# 3comando.net
KiCad netlist of a schematic drawn in EAGLE
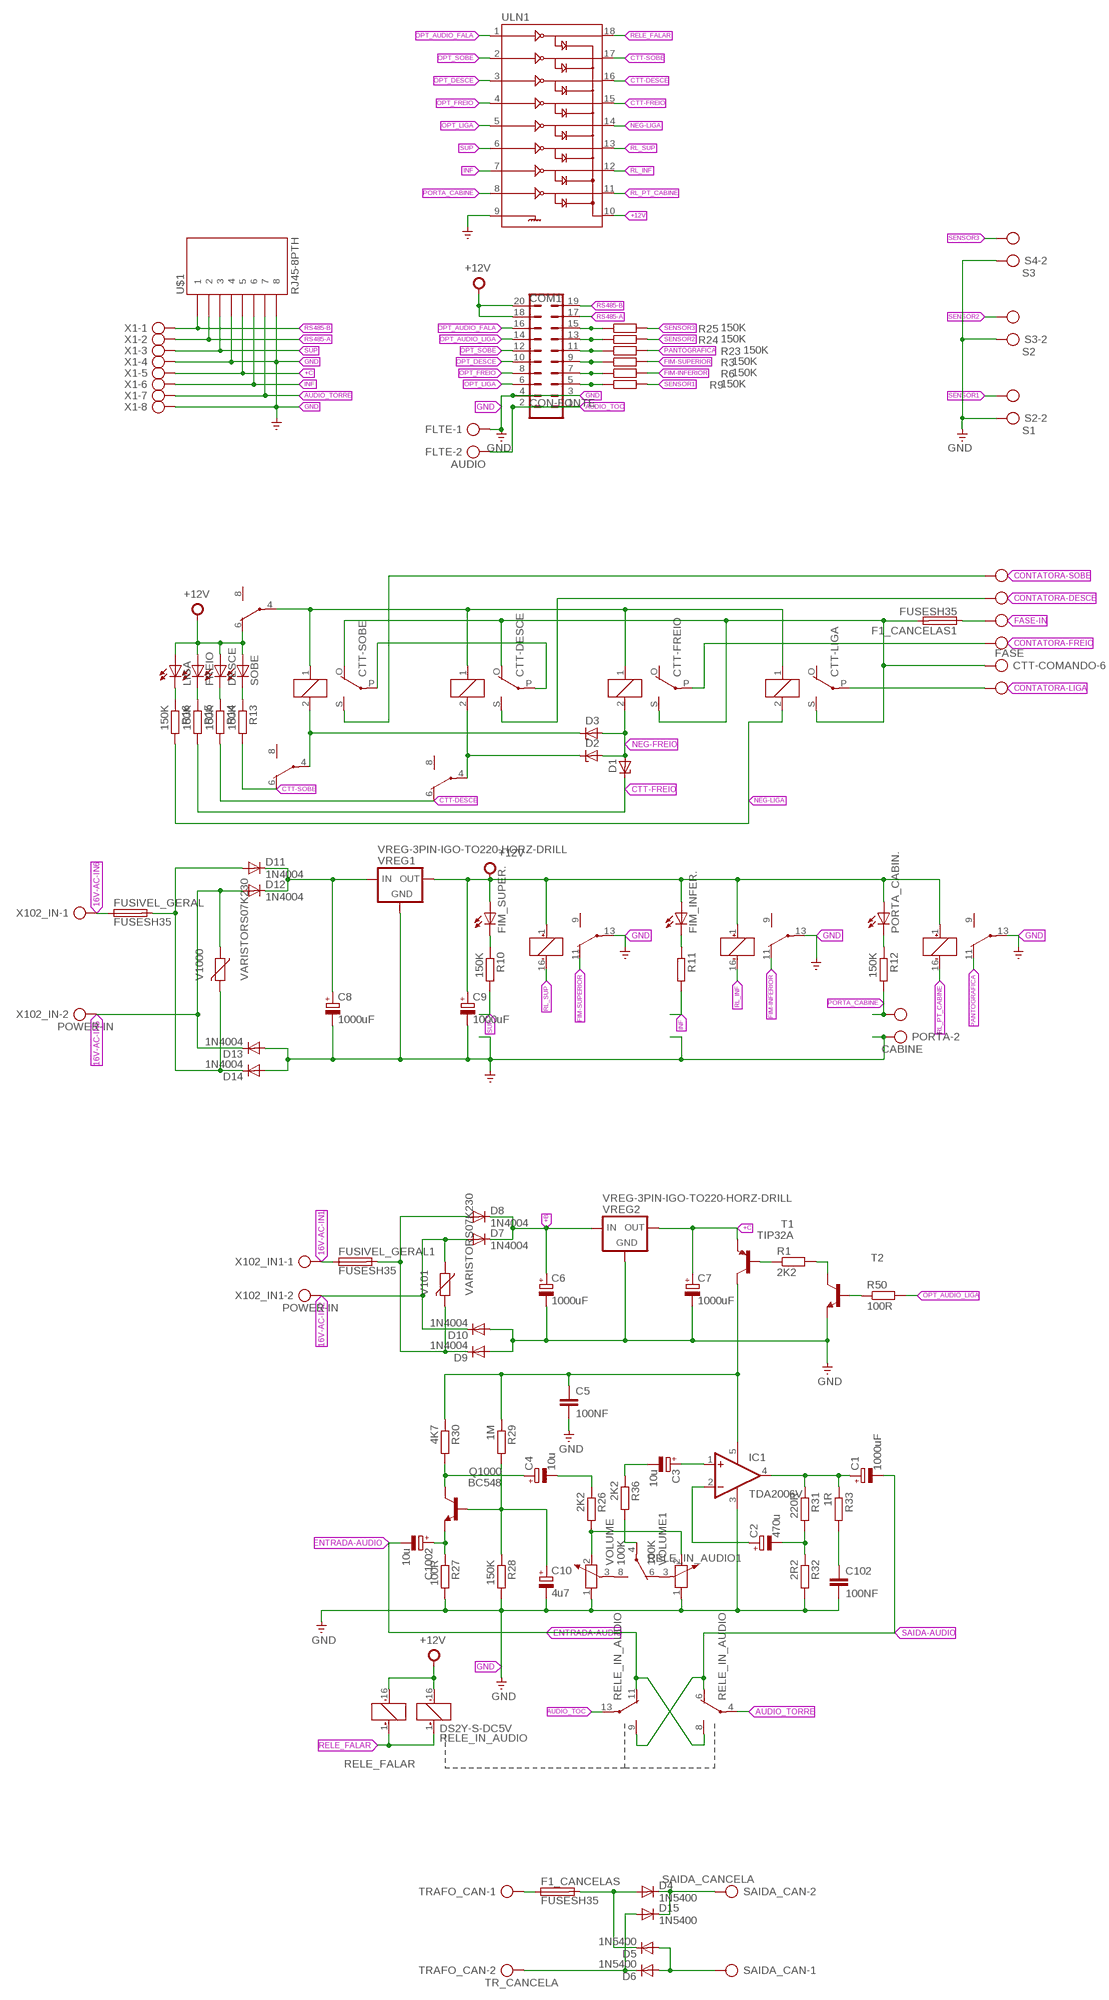
[diagram p0: schematic, sheet 1]

(export (version "E")
  (design (tool "Eeschema 10.0.6"))
  (components
    (comp (ref "C1")
      (value "1000uF")
      (footprint "eagle-import:TAP5-80")
      (libsource (lib "eagle-import") (part "CPOL-EUTAP5-80"))
    )
    (comp (ref "C2")
      (value "470u")
      (footprint "eagle-import:TAP5-80")
      (libsource (lib "eagle-import") (part "CPOL-EUTAP5-80"))
    )
    (comp (ref "C3")
      (value "10u")
      (footprint "eagle-import:TAP5-45")
      (libsource (lib "eagle-import") (part "CPOL-EUTAP5-45"))
    )
    (comp (ref "C4")
      (value "10u")
      (footprint "eagle-import:TAP5-45")
      (libsource (lib "eagle-import") (part "CPOL-EUTAP5-45"))
    )
    (comp (ref "C5")
      (value "100NF")
      (footprint "eagle-import:C050-030X075")
      (libsource (lib "eagle-import") (part "C-EU050-030X075"))
    )
    (comp (ref "C6")
      (value "1000uF")
      (footprint "eagle-import:TAP5-80")
      (libsource (lib "eagle-import") (part "CPOL-EUTAP5-80"))
    )
    (comp (ref "C7")
      (value "1000uF")
      (footprint "eagle-import:TAP5-80")
      (libsource (lib "eagle-import") (part "CPOL-EUTAP5-80"))
    )
    (comp (ref "C8")
      (value "1000uF")
      (footprint "eagle-import:TAP5-80")
      (libsource (lib "eagle-import") (part "CPOL-EUTAP5-80"))
    )
    (comp (ref "C9")
      (value "1000uF")
      (footprint "eagle-import:TAP5-80")
      (libsource (lib "eagle-import") (part "CPOL-EUTAP5-80"))
    )
    (comp (ref "C10")
      (value "4u7")
      (footprint "eagle-import:TAP5-45")
      (libsource (lib "eagle-import") (part "CPOL-EUTAP5-45"))
    )
    (comp (ref "C102")
      (value "100NF")
      (footprint "eagle-import:C050-030X075")
      (libsource (lib "eagle-import") (part "C-EU050-030X075"))
    )
    (comp (ref "C1002")
      (value "10u")
      (footprint "eagle-import:TAP5-45")
      (libsource (lib "eagle-import") (part "CPOL-EUTAP5-45"))
    )
    (comp (ref "COM1")
      (value "CON-FONTE")
      (footprint "eagle-import:ML20")
      (libsource (lib "eagle-import") (part "ML20"))
    )
    (comp (ref "CTT-COMANDO")
      (value "FASE")
      (footprint "eagle-import:AK500_6")
      (libsource (lib "eagle-import") (part "AK500/6"))
    )
    (comp (ref "CTT-DESCE")
      (value "G5L")
      (footprint "eagle-import:G5LE")
      (libsource (lib "eagle-import") (part "G5L"))
    )
    (comp (ref "CTT-FREIO")
      (value "G5L")
      (footprint "eagle-import:G5LE")
      (libsource (lib "eagle-import") (part "G5L"))
    )
    (comp (ref "CTT-LIGA")
      (value "G5L")
      (footprint "eagle-import:G5LE")
      (libsource (lib "eagle-import") (part "G5L"))
    )
    (comp (ref "CTT-SOBE")
      (value "G5L")
      (footprint "eagle-import:G5LE")
      (libsource (lib "eagle-import") (part "G5L"))
    )
    (comp (ref "D1")
      (value "ZENER-DIODEZD-7.5")
      (footprint "eagle-import:ZDIO-7.5")
      (libsource (lib "eagle-import") (part "ZENER-DIODEZD-7.5"))
    )
    (comp (ref "D2")
      (value "ZENER-DIODEZD-7.5")
      (footprint "eagle-import:ZDIO-7.5")
      (libsource (lib "eagle-import") (part "ZENER-DIODEZD-7.5"))
    )
    (comp (ref "D3")
      (value "ZENER-DIODEZD-7.5")
      (footprint "eagle-import:ZDIO-7.5")
      (libsource (lib "eagle-import") (part "ZENER-DIODEZD-7.5"))
    )
    (comp (ref "D4")
      (value "1N5400")
      (footprint "eagle-import:DO201-15")
      (libsource (lib "eagle-import") (part "1N5400"))
    )
    (comp (ref "D5")
      (value "1N5400")
      (footprint "eagle-import:DO201-15")
      (libsource (lib "eagle-import") (part "1N5400"))
    )
    (comp (ref "D6")
      (value "1N5400")
      (footprint "eagle-import:DO201-15")
      (libsource (lib "eagle-import") (part "1N5400"))
    )
    (comp (ref "D7")
      (value "1N4004")
      (footprint "eagle-import:DO41-10")
      (libsource (lib "eagle-import") (part "1N4004"))
    )
    (comp (ref "D8")
      (value "1N4004")
      (footprint "eagle-import:DO41-10")
      (libsource (lib "eagle-import") (part "1N4004"))
    )
    (comp (ref "D9")
      (value "1N4004")
      (footprint "eagle-import:DO41-10")
      (libsource (lib "eagle-import") (part "1N4004"))
    )
    (comp (ref "D10")
      (value "1N4004")
      (footprint "eagle-import:DO41-10")
      (libsource (lib "eagle-import") (part "1N4004"))
    )
    (comp (ref "D11")
      (value "1N4004")
      (footprint "eagle-import:DO41-10")
      (libsource (lib "eagle-import") (part "1N4004"))
    )
    (comp (ref "D12")
      (value "1N4004")
      (footprint "eagle-import:DO41-10")
      (libsource (lib "eagle-import") (part "1N4004"))
    )
    (comp (ref "D13")
      (value "1N4004")
      (footprint "eagle-import:DO41-10")
      (libsource (lib "eagle-import") (part "1N4004"))
    )
    (comp (ref "D14")
      (value "1N4004")
      (footprint "eagle-import:DO41-10")
      (libsource (lib "eagle-import") (part "1N4004"))
    )
    (comp (ref "D15")
      (value "1N5400")
      (footprint "eagle-import:DO201-15")
      (libsource (lib "eagle-import") (part "1N5400"))
    )
    (comp (ref "DESCE")
      (value "LED5MM")
      (footprint "eagle-import:LED5MM")
      (libsource (lib "eagle-import") (part "LED5MM"))
    )
    (comp (ref "F1_CANCELAS")
      (value "FUSESH35")
      (footprint "eagle-import:SH25")
      (libsource (lib "eagle-import") (part "FUSESH35"))
    )
    (comp (ref "F1_CANCELAS1")
      (value "FUSESH35")
      (footprint "eagle-import:SH25")
      (libsource (lib "eagle-import") (part "FUSESH35"))
    )
    (comp (ref "FIM_INFER.")
      (value "LED5MM")
      (footprint "eagle-import:LED5MM")
      (libsource (lib "eagle-import") (part "LED5MM"))
    )
    (comp (ref "FIM_SUPER.")
      (value "LED5MM")
      (footprint "eagle-import:LED5MM")
      (libsource (lib "eagle-import") (part "LED5MM"))
    )
    (comp (ref "FLTE")
      (value "AUDIO")
      (footprint "eagle-import:AK500_2")
      (libsource (lib "eagle-import") (part "AK500/2"))
    )
    (comp (ref "FREIO")
      (value "LED5MM")
      (footprint "eagle-import:LED5MM")
      (libsource (lib "eagle-import") (part "LED5MM"))
    )
    (comp (ref "FUSIVEL_GERAL")
      (value "FUSESH35")
      (footprint "eagle-import:SH25")
      (libsource (lib "eagle-import") (part "FUSESH35"))
    )
    (comp (ref "FUSIVEL_GERAL1")
      (value "FUSESH35")
      (footprint "eagle-import:SH25")
      (libsource (lib "eagle-import") (part "FUSESH35"))
    )
    (comp (ref "IC1")
      (value "TDA2006V")
      (footprint "eagle-import:CB360")
      (libsource (lib "eagle-import") (part "TDA2006V"))
    )
    (comp (ref "LIGA")
      (value "LED5MM")
      (footprint "eagle-import:LED5MM")
      (libsource (lib "eagle-import") (part "LED5MM"))
    )
    (comp (ref "PORTA")
      (value "CABINE")
      (footprint "eagle-import:AK500_2")
      (libsource (lib "eagle-import") (part "AK500/2"))
    )
    (comp (ref "PORTA_CABIN.")
      (value "LED5MM")
      (footprint "eagle-import:LED5MM")
      (libsource (lib "eagle-import") (part "LED5MM"))
    )
    (comp (ref "PORTA_CABINE")
      (value "DS2Y-S-DC5V")
      (footprint "eagle-import:DS2Y")
      (libsource (lib "eagle-import") (part "DS2Y-S-DC5V"))
    )
    (comp (ref "Q1000")
      (value "BC548")
      (footprint "eagle-import:TO92-EBC")
      (libsource (lib "eagle-import") (part "BC548"))
    )
    (comp (ref "R1")
      (value "2K2")
      (footprint "eagle-import:0207_10")
      (libsource (lib "eagle-import") (part "R-EU_0207/10"))
    )
    (comp (ref "R3")
      (value "150K")
      (footprint "eagle-import:0207_10")
      (libsource (lib "eagle-import") (part "R-EU_0207/10"))
    )
    (comp (ref "R6")
      (value "150K")
      (footprint "eagle-import:0207_10")
      (libsource (lib "eagle-import") (part "R-EU_0207/10"))
    )
    (comp (ref "R9")
      (value "150K")
      (footprint "eagle-import:0207_10")
      (libsource (lib "eagle-import") (part "R-EU_0207/10"))
    )
    (comp (ref "R10")
      (value "150K")
      (footprint "eagle-import:0207_10")
      (libsource (lib "eagle-import") (part "R-EU_0207/10"))
    )
    (comp (ref "R11")
      (value "150K")
      (footprint "eagle-import:0207_10")
      (libsource (lib "eagle-import") (part "R-EU_0207/10"))
    )
    (comp (ref "R12")
      (value "150K")
      (footprint "eagle-import:0207_10")
      (libsource (lib "eagle-import") (part "R-EU_0207/10"))
    )
    (comp (ref "R13")
      (value "150K")
      (footprint "eagle-import:0207_10")
      (libsource (lib "eagle-import") (part "R-EU_0207/10"))
    )
    (comp (ref "R14")
      (value "150K")
      (footprint "eagle-import:0207_10")
      (libsource (lib "eagle-import") (part "R-EU_0207/10"))
    )
    (comp (ref "R15")
      (value "150K")
      (footprint "eagle-import:0207_10")
      (libsource (lib "eagle-import") (part "R-EU_0207/10"))
    )
    (comp (ref "R16")
      (value "150K")
      (footprint "eagle-import:0207_10")
      (libsource (lib "eagle-import") (part "R-EU_0207/10"))
    )
    (comp (ref "R23")
      (value "150K")
      (footprint "eagle-import:0207_10")
      (libsource (lib "eagle-import") (part "R-EU_0207/10"))
    )
    (comp (ref "R24")
      (value "150K")
      (footprint "eagle-import:0207_10")
      (libsource (lib "eagle-import") (part "R-EU_0207/10"))
    )
    (comp (ref "R25")
      (value "150K")
      (footprint "eagle-import:0207_10")
      (libsource (lib "eagle-import") (part "R-EU_0207/10"))
    )
    (comp (ref "R26")
      (value "2K2")
      (footprint "eagle-import:0207_10")
      (libsource (lib "eagle-import") (part "R-EU_0207/10"))
    )
    (comp (ref "R27")
      (value "100R")
      (footprint "eagle-import:0207_10")
      (libsource (lib "eagle-import") (part "R-EU_0207/10"))
    )
    (comp (ref "R28")
      (value "150K")
      (footprint "eagle-import:0207_10")
      (libsource (lib "eagle-import") (part "R-EU_0207/10"))
    )
    (comp (ref "R29")
      (value "1M")
      (footprint "eagle-import:0207_10")
      (libsource (lib "eagle-import") (part "R-EU_0207/10"))
    )
    (comp (ref "R30")
      (value "4K7")
      (footprint "eagle-import:0207_10")
      (libsource (lib "eagle-import") (part "R-EU_0207/10"))
    )
    (comp (ref "R31")
      (value "220R")
      (footprint "eagle-import:0207_10")
      (libsource (lib "eagle-import") (part "R-EU_0207/10"))
    )
    (comp (ref "R32")
      (value "2R2")
      (footprint "eagle-import:0207_10")
      (libsource (lib "eagle-import") (part "R-EU_0207/10"))
    )
    (comp (ref "R33")
      (value "1R")
      (footprint "eagle-import:0207_10")
      (libsource (lib "eagle-import") (part "R-EU_0207/10"))
    )
    (comp (ref "R36")
      (value "2K2")
      (footprint "eagle-import:0207_10")
      (libsource (lib "eagle-import") (part "R-EU_0207/10"))
    )
    (comp (ref "R50")
      (value "100R")
      (footprint "eagle-import:0207_10")
      (libsource (lib "eagle-import") (part "R-EU_0207/10"))
    )
    (comp (ref "RELE_IN_AUDIO")
      (value "DS2Y-S-DC5V")
      (footprint "eagle-import:DS2Y")
      (libsource (lib "eagle-import") (part "DS2Y-S-DC5V"))
    )
    (comp (ref "RELE_IN_AUDIO1")
      (value "DS2Y-S-DC5V")
      (footprint "eagle-import:DS2Y")
      (libsource (lib "eagle-import") (part "DS2Y-S-DC5V"))
    )
    (comp (ref "RL_FIM_INFERIOR")
      (value "DS2Y-S-DC5V")
      (footprint "eagle-import:DS2Y")
      (libsource (lib "eagle-import") (part "DS2Y-S-DC5V"))
    )
    (comp (ref "RL_FIM_SUPERIOR")
      (value "DS2Y-S-DC5V")
      (footprint "eagle-import:DS2Y")
      (libsource (lib "eagle-import") (part "DS2Y-S-DC5V"))
    )
    (comp (ref "S2")
      (value "S1")
      (footprint "eagle-import:AK500_2")
      (libsource (lib "eagle-import") (part "AK500/2"))
    )
    (comp (ref "S3")
      (value "S2")
      (footprint "eagle-import:AK500_2")
      (libsource (lib "eagle-import") (part "AK500/2"))
    )
    (comp (ref "S4")
      (value "S3")
      (footprint "eagle-import:AK500_2")
      (libsource (lib "eagle-import") (part "AK500/2"))
    )
    (comp (ref "SAIDA_CAN")
      (value "SAIDA_CANCELA")
      (footprint "eagle-import:AK500_2")
      (libsource (lib "eagle-import") (part "AK500/2"))
    )
    (comp (ref "SOBE")
      (value "LED5MM")
      (footprint "eagle-import:LED5MM")
      (libsource (lib "eagle-import") (part "LED5MM"))
    )
    (comp (ref "T1")
      (value "TIP32A")
      (footprint "eagle-import:TO220")
      (libsource (lib "eagle-import") (part "TIP32A"))
    )
    (comp (ref "T2")
      (value "BC548-NPN-TO92-CBE")
      (footprint "eagle-import:TO92-CBE")
      (libsource (lib "eagle-import") (part "-NPN-TO92-CBEBC548"))
    )
    (comp (ref "TRAFO_CAN")
      (value "TR_CANCELA")
      (footprint "eagle-import:AK500_2")
      (libsource (lib "eagle-import") (part "AK500/2"))
    )
    (comp (ref "U$1")
      (value "RJ45-8PTH")
      (footprint "eagle-import:RJ45-8")
      (libsource (lib "eagle-import") (part "RJ45-8PTH"))
    )
    (comp (ref "ULN1")
      (value "ULN2803DIP")
      (footprint "eagle-import:DIL18")
      (libsource (lib "eagle-import") (part "ULN2803DIP"))
    )
    (comp (ref "V101")
      (value "VARISTORS07K230")
      (footprint "eagle-import:S07K230")
      (libsource (lib "eagle-import") (part "VARISTORS07K230"))
    )
    (comp (ref "V1000")
      (value "VARISTORS07K230")
      (footprint "eagle-import:S07K230")
      (libsource (lib "eagle-import") (part "VARISTORS07K230"))
    )
    (comp (ref "VOLUME")
      (value "100K")
      (footprint "eagle-import:PT-10")
      (libsource (lib "eagle-import") (part "POTENTIOMETER_PT-10"))
    )
    (comp (ref "VOLUME1")
      (value "100K")
      (footprint "eagle-import:PT-10")
      (libsource (lib "eagle-import") (part "POTENTIOMETER_PT-10"))
    )
    (comp (ref "VREG1")
      (value "VREG-3PIN-IGO-TO220-HORZ-DRILL")
      (footprint "eagle-import:TO220-HORZ-DRILL")
      (libsource (lib "eagle-import") (part "VREG-3PIN-IGO-TO220-HORZ-DRILL"))
    )
    (comp (ref "VREG2")
      (value "VREG-3PIN-IGO-TO220-HORZ-DRILL")
      (footprint "eagle-import:TO220-HORZ-DRILL")
      (libsource (lib "eagle-import") (part "VREG-3PIN-IGO-TO220-HORZ-DRILL"))
    )
    (comp (ref "X1")
      (value "RS485_CNT")
      (footprint "eagle-import:AK500_8")
      (libsource (lib "eagle-import") (part "AK500/8"))
    )
    (comp (ref "X102_IN")
      (value "POWER-IN")
      (footprint "eagle-import:AK500_2")
      (libsource (lib "eagle-import") (part "AK500/2"))
    )
    (comp (ref "X102_IN1")
      (value "POWER-IN")
      (footprint "eagle-import:AK500_2")
      (libsource (lib "eagle-import") (part "AK500/2"))
    )
  )
  (nets
    (net (code "1") (name "+12V") (class "Default")
      (node (ref "C9") (pin "+") (pinfunction "+_+") (pintype "passive"))
      (node (ref "COM1") (pin "18") (pinfunction "18_18") (pintype "passive"))
      (node (ref "COM1") (pin "20") (pinfunction "20_20") (pintype "passive"))
      (node (ref "DESCE") (pin "A") (pinfunction "A_A") (pintype "passive"))
      (node (ref "FIM_INFER.") (pin "A") (pinfunction "A_A") (pintype "passive"))
      (node (ref "FIM_SUPER.") (pin "A") (pinfunction "A_A") (pintype "passive"))
      (node (ref "FREIO") (pin "A") (pinfunction "A_A") (pintype "passive"))
      (node (ref "LIGA") (pin "A") (pinfunction "A_A") (pintype "passive"))
      (node (ref "PORTA_CABIN.") (pin "A") (pinfunction "A_A") (pintype "passive"))
      (node (ref "PORTA_CABINE") (pin "1") (pinfunction "+_1") (pintype "passive"))
      (node (ref "PORTA_CABINE") (pin "6") (pinfunction "O_6") (pintype "passive"))
      (node (ref "RELE_IN_AUDIO") (pin "16") (pinfunction "-_16") (pintype "passive"))
      (node (ref "RELE_IN_AUDIO1") (pin "16") (pinfunction "-_16") (pintype "passive"))
      (node (ref "RL_FIM_INFERIOR") (pin "1") (pinfunction "+_1") (pintype "passive"))
      (node (ref "RL_FIM_SUPERIOR") (pin "1") (pinfunction "+_1") (pintype "passive"))
      (node (ref "SOBE") (pin "A") (pinfunction "A_A") (pintype "passive"))
      (node (ref "ULN1") (pin "10") (pinfunction "10_10") (pintype "bidirectional"))
      (node (ref "VREG1") (pin "3") (pinfunction "OUT_3") (pintype "power_in"))
    )
    (net (code "2") (name "+B") (class "Default")
      (node (ref "C6") (pin "+") (pinfunction "+_+") (pintype "passive"))
      (node (ref "D7") (pin "C") (pinfunction "C_C") (pintype "passive"))
      (node (ref "D8") (pin "C") (pinfunction "C_C") (pintype "passive"))
      (node (ref "VREG2") (pin "1") (pinfunction "IN_1") (pintype "power_in"))
    )
    (net (code "3") (name "+C") (class "Default")
      (node (ref "C7") (pin "+") (pinfunction "+_+") (pintype "passive"))
      (node (ref "T1") (pin "3") (pinfunction "E_3") (pintype "passive"))
      (node (ref "U$1") (pin "5") (pinfunction "5_5") (pintype "bidirectional"))
      (node (ref "VREG2") (pin "3") (pinfunction "OUT_3") (pintype "power_in"))
      (node (ref "X1") (pin "5") (pinfunction "KL_5") (pintype "passive"))
    )
    (net (code "4") (name "16V-AC-IN1") (class "Default")
      (node (ref "FUSIVEL_GERAL1") (pin "1") (pinfunction "1_1") (pintype "passive"))
      (node (ref "X102_IN1") (pin "1") (pinfunction "KL_1") (pintype "passive"))
    )
    (net (code "5") (name "16V-AC-IN2") (class "Default")
      (node (ref "D10") (pin "C") (pinfunction "C_C") (pintype "passive"))
      (node (ref "D7") (pin "A") (pinfunction "A_A") (pintype "passive"))
      (node (ref "V101") (pin "1") (pinfunction "1_1") (pintype "passive"))
      (node (ref "X102_IN1") (pin "2") (pinfunction "KL_2") (pintype "passive"))
    )
    (net (code "6") (name "16V-AC-IN5") (class "Default")
      (node (ref "D12") (pin "A") (pinfunction "A_A") (pintype "passive"))
      (node (ref "D13") (pin "C") (pinfunction "C_C") (pintype "passive"))
      (node (ref "V1000") (pin "1") (pinfunction "1_1") (pintype "passive"))
      (node (ref "X102_IN") (pin "2") (pinfunction "KL_2") (pintype "passive"))
    )
    (net (code "7") (name "16V-AC-IN6") (class "Default")
      (node (ref "FUSIVEL_GERAL") (pin "1") (pinfunction "1_1") (pintype "passive"))
      (node (ref "X102_IN") (pin "1") (pinfunction "KL_1") (pintype "passive"))
    )
    (net (code "8") (name "AUDIO_TOC") (class "Default")
      (node (ref "COM1") (pin "1") (pinfunction "1_1") (pintype "passive"))
      (node (ref "COM1") (pin "2") (pinfunction "2_2") (pintype "passive"))
      (node (ref "FLTE") (pin "2") (pinfunction "KL_2") (pintype "passive"))
      (node (ref "RELE_IN_AUDIO") (pin "13") (pinfunction "P_13") (pintype "passive"))
    )
    (net (code "9") (name "AUDIO_TORRE") (class "Default")
      (node (ref "RELE_IN_AUDIO") (pin "4") (pinfunction "P_4") (pintype "passive"))
      (node (ref "U$1") (pin "7") (pinfunction "7_7") (pintype "bidirectional"))
      (node (ref "X1") (pin "7") (pinfunction "KL_7") (pintype "passive"))
    )
    (net (code "10") (name "CONTATORA-DESCE") (class "Default")
      (node (ref "CTT-COMANDO") (pin "4") (pinfunction "KL_4") (pintype "passive"))
      (node (ref "CTT-DESCE") (pin "S") (pinfunction "S_S") (pintype "passive"))
    )
    (net (code "11") (name "CONTATORA-FREIO") (class "Default")
      (node (ref "CTT-COMANDO") (pin "3") (pinfunction "KL_3") (pintype "passive"))
      (node (ref "CTT-FREIO") (pin "P") (pinfunction "P_P") (pintype "passive"))
    )
    (net (code "12") (name "CONTATORA-LIGA") (class "Default")
      (node (ref "CTT-COMANDO") (pin "2") (pinfunction "KL_2") (pintype "passive"))
      (node (ref "CTT-LIGA") (pin "P") (pinfunction "P_P") (pintype "passive"))
    )
    (net (code "13") (name "CONTATORA-SOBE") (class "Default")
      (node (ref "CTT-COMANDO") (pin "5") (pinfunction "KL_5") (pintype "passive"))
      (node (ref "CTT-SOBE") (pin "S") (pinfunction "S_S") (pintype "passive"))
    )
    (net (code "14") (name "CTT-DESCE") (class "Default")
      (node (ref "R14") (pin "2") (pinfunction "2_2") (pintype "passive"))
      (node (ref "RL_FIM_INFERIOR") (pin "6") (pinfunction "O_6") (pintype "passive"))
      (node (ref "ULN1") (pin "16") (pinfunction "16_16") (pintype "bidirectional"))
    )
    (net (code "15") (name "CTT-FREIO") (class "Default")
      (node (ref "D1") (pin "C") (pinfunction "C_C") (pintype "passive"))
      (node (ref "R15") (pin "2") (pinfunction "2_2") (pintype "passive"))
      (node (ref "ULN1") (pin "15") (pinfunction "15_15") (pintype "bidirectional"))
    )
    (net (code "16") (name "CTT-SOBE") (class "Default")
      (node (ref "R13") (pin "2") (pinfunction "2_2") (pintype "passive"))
      (node (ref "RL_FIM_SUPERIOR") (pin "6") (pinfunction "O_6") (pintype "passive"))
      (node (ref "ULN1") (pin "17") (pinfunction "17_17") (pintype "bidirectional"))
    )
    (net (code "17") (name "ENTRADA-AUDIO") (class "Default")
      (node (ref "C1002") (pin "-") (pinfunction "-_-") (pintype "passive"))
      (node (ref "RELE_IN_AUDIO") (pin "11") (pinfunction "O_11") (pintype "passive"))
      (node (ref "RELE_IN_AUDIO") (pin "8") (pinfunction "S_8") (pintype "passive"))
    )
    (net (code "18") (name "FASE-IN") (class "Default")
      (node (ref "CTT-COMANDO") (pin "1") (pinfunction "KL_1") (pintype "passive"))
      (node (ref "F1_CANCELAS1") (pin "1") (pinfunction "1_1") (pintype "passive"))
    )
    (net (code "19") (name "FIM-INFERIOR") (class "Default")
      (node (ref "R6") (pin "2") (pinfunction "2_2") (pintype "passive"))
      (node (ref "RL_FIM_INFERIOR") (pin "11") (pinfunction "O_11") (pintype "passive"))
    )
    (net (code "20") (name "FIM-SUPERIOR") (class "Default")
      (node (ref "R3") (pin "2") (pinfunction "2_2") (pintype "passive"))
      (node (ref "RL_FIM_SUPERIOR") (pin "11") (pinfunction "O_11") (pintype "passive"))
    )
    (net (code "21") (name "GND") (class "Default")
      (node (ref "C10") (pin "-") (pinfunction "-_-") (pintype "passive"))
      (node (ref "C102") (pin "2") (pinfunction "2_2") (pintype "passive"))
      (node (ref "C5") (pin "2") (pinfunction "2_2") (pintype "passive"))
      (node (ref "C6") (pin "-") (pinfunction "-_-") (pintype "passive"))
      (node (ref "C7") (pin "-") (pinfunction "-_-") (pintype "passive"))
      (node (ref "C8") (pin "-") (pinfunction "-_-") (pintype "passive"))
      (node (ref "C9") (pin "-") (pinfunction "-_-") (pintype "passive"))
      (node (ref "COM1") (pin "3") (pinfunction "3_3") (pintype "passive"))
      (node (ref "COM1") (pin "4") (pinfunction "4_4") (pintype "passive"))
      (node (ref "D10") (pin "A") (pinfunction "A_A") (pintype "passive"))
      (node (ref "D13") (pin "A") (pinfunction "A_A") (pintype "passive"))
      (node (ref "D14") (pin "A") (pinfunction "A_A") (pintype "passive"))
      (node (ref "D9") (pin "A") (pinfunction "A_A") (pintype "passive"))
      (node (ref "FLTE") (pin "1") (pinfunction "KL_1") (pintype "passive"))
      (node (ref "IC1") (pin "3") (pinfunction "V-_3") (pintype "power_in"))
      (node (ref "PORTA") (pin "2") (pinfunction "KL_2") (pintype "passive"))
      (node (ref "PORTA_CABINE") (pin "13") (pinfunction "P_13") (pintype "passive"))
      (node (ref "R27") (pin "2") (pinfunction "2_2") (pintype "passive"))
      (node (ref "R28") (pin "2") (pinfunction "2_2") (pintype "passive"))
      (node (ref "R32") (pin "2") (pinfunction "2_2") (pintype "passive"))
      (node (ref "RL_FIM_INFERIOR") (pin "13") (pinfunction "P_13") (pintype "passive"))
      (node (ref "RL_FIM_SUPERIOR") (pin "13") (pinfunction "P_13") (pintype "passive"))
      (node (ref "S2") (pin "2") (pinfunction "KL_2") (pintype "passive"))
      (node (ref "S3") (pin "2") (pinfunction "KL_2") (pintype "passive"))
      (node (ref "S4") (pin "2") (pinfunction "KL_2") (pintype "passive"))
      (node (ref "T2") (pin "E") (pinfunction "E_E") (pintype "passive"))
      (node (ref "U$1") (pin "4") (pinfunction "4_4") (pintype "bidirectional"))
      (node (ref "U$1") (pin "8") (pinfunction "8_8") (pintype "bidirectional"))
      (node (ref "ULN1") (pin "9") (pinfunction "9_9") (pintype "bidirectional"))
      (node (ref "VOLUME") (pin "1") (pinfunction "1_1") (pintype "passive"))
      (node (ref "VOLUME1") (pin "1") (pinfunction "1_1") (pintype "passive"))
      (node (ref "VREG1") (pin "2") (pinfunction "GND_2") (pintype "power_in"))
      (node (ref "VREG2") (pin "2") (pinfunction "GND_2") (pintype "power_in"))
      (node (ref "X1") (pin "4") (pinfunction "KL_4") (pintype "passive"))
      (node (ref "X1") (pin "8") (pinfunction "KL_8") (pintype "passive"))
    )
    (net (code "22") (name "INF") (class "Default")
      (node (ref "R11") (pin "2") (pinfunction "2_2") (pintype "passive"))
      (node (ref "U$1") (pin "6") (pinfunction "6_6") (pintype "bidirectional"))
      (node (ref "ULN1") (pin "7") (pinfunction "7_7") (pintype "bidirectional"))
      (node (ref "X1") (pin "6") (pinfunction "KL_6") (pintype "passive"))
    )
    (net (code "23") (name "NEG-FREIO") (class "Default")
      (node (ref "CTT-FREIO") (pin "2") (pinfunction "2_2") (pintype "passive"))
      (node (ref "D1") (pin "A") (pinfunction "A_A") (pintype "passive"))
      (node (ref "D2") (pin "A") (pinfunction "A_A") (pintype "passive"))
      (node (ref "D3") (pin "A") (pinfunction "A_A") (pintype "passive"))
    )
    (net (code "24") (name "NEG-LIGA") (class "Default")
      (node (ref "CTT-LIGA") (pin "2") (pinfunction "2_2") (pintype "passive"))
      (node (ref "R16") (pin "2") (pinfunction "2_2") (pintype "passive"))
      (node (ref "ULN1") (pin "14") (pinfunction "14_14") (pintype "bidirectional"))
    )
    (net (code "25") (name "Net-(C2-Pad-)") (class "Default")
      (node (ref "C2") (pin "-") (pinfunction "-_-") (pintype "passive"))
      (node (ref "R31") (pin "2") (pinfunction "2_2") (pintype "passive"))
      (node (ref "R32") (pin "1") (pinfunction "1_1") (pintype "passive"))
    )
    (net (code "26") (name "Net-(C3-Pad-)") (class "Default")
      (node (ref "C3") (pin "-") (pinfunction "-_-") (pintype "passive"))
      (node (ref "R36") (pin "1") (pinfunction "1_1") (pintype "passive"))
    )
    (net (code "27") (name "Net-(C4-Pad+)") (class "Default")
      (node (ref "C4") (pin "+") (pinfunction "+_+") (pintype "passive"))
      (node (ref "Q1000") (pin "C") (pinfunction "C_C") (pintype "passive"))
      (node (ref "R30") (pin "2") (pinfunction "2_2") (pintype "passive"))
    )
    (net (code "28") (name "Net-(C4-Pad-)") (class "Default")
      (node (ref "C4") (pin "-") (pinfunction "-_-") (pintype "passive"))
      (node (ref "R26") (pin "1") (pinfunction "1_1") (pintype "passive"))
    )
    (net (code "29") (name "Net-(C10-Pad+)") (class "Default")
      (node (ref "C10") (pin "+") (pinfunction "+_+") (pintype "passive"))
      (node (ref "Q1000") (pin "B") (pinfunction "B_B") (pintype "passive"))
      (node (ref "R28") (pin "1") (pinfunction "1_1") (pintype "passive"))
      (node (ref "R29") (pin "2") (pinfunction "2_2") (pintype "passive"))
    )
    (net (code "30") (name "Net-(C102-Pad1)") (class "Default")
      (node (ref "C102") (pin "1") (pinfunction "1_1") (pintype "passive"))
      (node (ref "R33") (pin "2") (pinfunction "2_2") (pintype "passive"))
    )
    (net (code "31") (name "Net-(C1002-Pad+)") (class "Default")
      (node (ref "C1002") (pin "+") (pinfunction "+_+") (pintype "passive"))
      (node (ref "Q1000") (pin "E") (pinfunction "E_E") (pintype "passive"))
      (node (ref "R27") (pin "1") (pinfunction "1_1") (pintype "passive"))
    )
    (net (code "32") (name "Net-(COM1-Pad5)") (class "Default")
      (node (ref "COM1") (pin "5") (pinfunction "5_5") (pintype "passive"))
      (node (ref "R9") (pin "1") (pinfunction "1_1") (pintype "passive"))
    )
    (net (code "33") (name "Net-(COM1-Pad7)") (class "Default")
      (node (ref "COM1") (pin "7") (pinfunction "7_7") (pintype "passive"))
      (node (ref "R6") (pin "1") (pinfunction "1_1") (pintype "passive"))
    )
    (net (code "34") (name "Net-(COM1-Pad9)") (class "Default")
      (node (ref "COM1") (pin "9") (pinfunction "9_9") (pintype "passive"))
      (node (ref "R3") (pin "1") (pinfunction "1_1") (pintype "passive"))
    )
    (net (code "35") (name "Net-(COM1-Pad11)") (class "Default")
      (node (ref "COM1") (pin "11") (pinfunction "11_11") (pintype "passive"))
      (node (ref "R23") (pin "1") (pinfunction "1_1") (pintype "passive"))
    )
    (net (code "36") (name "Net-(COM1-Pad13)") (class "Default")
      (node (ref "COM1") (pin "13") (pinfunction "13_13") (pintype "passive"))
      (node (ref "R24") (pin "1") (pinfunction "1_1") (pintype "passive"))
    )
    (net (code "37") (name "Net-(COM1-Pad15)") (class "Default")
      (node (ref "COM1") (pin "15") (pinfunction "15_15") (pintype "passive"))
      (node (ref "R25") (pin "1") (pinfunction "1_1") (pintype "passive"))
    )
    (net (code "38") (name "Net-(CTT-COMANDOF-KL)") (class "Default")
      (node (ref "CTT-COMANDO") (pin "6") (pinfunction "KL_6") (pintype "passive"))
      (node (ref "CTT-DESCE") (pin "O") (pinfunction "O_O") (pintype "passive"))
      (node (ref "CTT-FREIO") (pin "S") (pinfunction "S_S") (pintype "passive"))
      (node (ref "CTT-LIGA") (pin "S") (pinfunction "S_S") (pintype "passive"))
      (node (ref "CTT-SOBE") (pin "O") (pinfunction "O_O") (pintype "passive"))
      (node (ref "F1_CANCELAS1") (pin "2") (pinfunction "2_2") (pintype "passive"))
    )
    (net (code "39") (name "Net-(CTT-DESCE-PadP)") (class "Default")
      (node (ref "CTT-DESCE") (pin "P") (pinfunction "P_P") (pintype "passive"))
      (node (ref "CTT-SOBE") (pin "P") (pinfunction "P_P") (pintype "passive"))
    )
    (net (code "40") (name "Net-(D4-PadA)") (class "Default")
      (node (ref "D4") (pin "A") (pinfunction "A_A") (pintype "passive"))
      (node (ref "D5") (pin "C") (pinfunction "C_C") (pintype "passive"))
      (node (ref "F1_CANCELAS") (pin "2") (pinfunction "2_2") (pintype "passive"))
    )
    (net (code "41") (name "Net-(D8-PadA)") (class "Default")
      (node (ref "D8") (pin "A") (pinfunction "A_A") (pintype "passive"))
      (node (ref "D9") (pin "C") (pinfunction "C_C") (pintype "passive"))
      (node (ref "FUSIVEL_GERAL1") (pin "2") (pinfunction "2_2") (pintype "passive"))
      (node (ref "V101") (pin "2") (pinfunction "2_2") (pintype "passive"))
    )
    (net (code "42") (name "Net-(D11-PadA)") (class "Default")
      (node (ref "D11") (pin "A") (pinfunction "A_A") (pintype "passive"))
      (node (ref "D14") (pin "C") (pinfunction "C_C") (pintype "passive"))
      (node (ref "FUSIVEL_GERAL") (pin "2") (pinfunction "2_2") (pintype "passive"))
      (node (ref "V1000") (pin "2") (pinfunction "2_2") (pintype "passive"))
    )
    (net (code "43") (name "Net-(DESCE-C)") (class "Default")
      (node (ref "DESCE") (pin "K") (pinfunction "C_K") (pintype "passive"))
      (node (ref "R14") (pin "1") (pinfunction "1_1") (pintype "passive"))
    )
    (net (code "44") (name "Net-(FIM_INFER.-C)") (class "Default")
      (node (ref "FIM_INFER.") (pin "K") (pinfunction "C_K") (pintype "passive"))
      (node (ref "R11") (pin "1") (pinfunction "1_1") (pintype "passive"))
    )
    (net (code "45") (name "Net-(FIM_SUPER.-C)") (class "Default")
      (node (ref "FIM_SUPER.") (pin "K") (pinfunction "C_K") (pintype "passive"))
      (node (ref "R10") (pin "1") (pinfunction "1_1") (pintype "passive"))
    )
    (net (code "46") (name "Net-(FREIO-C)") (class "Default")
      (node (ref "FREIO") (pin "K") (pinfunction "C_K") (pintype "passive"))
      (node (ref "R15") (pin "1") (pinfunction "1_1") (pintype "passive"))
    )
    (net (code "47") (name "Net-(IC1-+IN)") (class "Default")
      (node (ref "C3") (pin "+") (pinfunction "+_+") (pintype "passive"))
      (node (ref "IC1") (pin "1") (pinfunction "+IN_1") (pintype "input"))
    )
    (net (code "48") (name "Net-(IC1--IN)") (class "Default")
      (node (ref "C2") (pin "+") (pinfunction "+_+") (pintype "passive"))
      (node (ref "IC1") (pin "2") (pinfunction "-IN_2") (pintype "input"))
    )
    (net (code "49") (name "Net-(IC1-OUT)") (class "Default")
      (node (ref "C1") (pin "+") (pinfunction "+_+") (pintype "passive"))
      (node (ref "IC1") (pin "4") (pinfunction "OUT_4") (pintype "output"))
      (node (ref "R31") (pin "1") (pinfunction "1_1") (pintype "passive"))
      (node (ref "R33") (pin "1") (pinfunction "1_1") (pintype "passive"))
    )
    (net (code "50") (name "Net-(IC1-V+)") (class "Default")
      (node (ref "C5") (pin "1") (pinfunction "1_1") (pintype "passive"))
      (node (ref "IC1") (pin "5") (pinfunction "V+_5") (pintype "power_in"))
      (node (ref "R29") (pin "1") (pinfunction "1_1") (pintype "passive"))
      (node (ref "R30") (pin "1") (pinfunction "1_1") (pintype "passive"))
      (node (ref "T1") (pin "2") (pinfunction "C_2") (pintype "passive"))
    )
    (net (code "51") (name "Net-(LIGA-C)") (class "Default")
      (node (ref "LIGA") (pin "K") (pinfunction "C_K") (pintype "passive"))
      (node (ref "R16") (pin "1") (pinfunction "1_1") (pintype "passive"))
    )
    (net (code "52") (name "Net-(PORTA_CABIN.-C)") (class "Default")
      (node (ref "PORTA_CABIN.") (pin "K") (pinfunction "C_K") (pintype "passive"))
      (node (ref "R12") (pin "1") (pinfunction "1_1") (pintype "passive"))
    )
    (net (code "53") (name "Net-(PORTA_CABINEB-P)") (class "Default")
      (node (ref "CTT-DESCE") (pin "1") (pinfunction "1_1") (pintype "passive"))
      (node (ref "CTT-FREIO") (pin "1") (pinfunction "1_1") (pintype "passive"))
      (node (ref "CTT-LIGA") (pin "1") (pinfunction "1_1") (pintype "passive"))
      (node (ref "CTT-SOBE") (pin "1") (pinfunction "1_1") (pintype "passive"))
      (node (ref "PORTA_CABINE") (pin "4") (pinfunction "P_4") (pintype "passive"))
    )
    (net (code "54") (name "Net-(R1-Pad2)") (class "Default")
      (node (ref "R1") (pin "2") (pinfunction "2_2") (pintype "passive"))
      (node (ref "T2") (pin "C") (pinfunction "C_C") (pintype "passive"))
    )
    (net (code "55") (name "Net-(R26-Pad2)") (class "Default")
      (node (ref "R26") (pin "2") (pinfunction "2_2") (pintype "passive"))
      (node (ref "VOLUME") (pin "2") (pinfunction "2_2") (pintype "passive"))
      (node (ref "VOLUME1") (pin "2") (pinfunction "2_2") (pintype "passive"))
    )
    (net (code "56") (name "Net-(R50-Pad1)") (class "Default")
      (node (ref "R50") (pin "1") (pinfunction "1_1") (pintype "passive"))
      (node (ref "T2") (pin "B") (pinfunction "B_B") (pintype "passive"))
    )
    (net (code "57") (name "Net-(RELE_IN_AUDIO1B-O)") (class "Default")
      (node (ref "RELE_IN_AUDIO1") (pin "6") (pinfunction "O_6") (pintype "passive"))
      (node (ref "VOLUME1") (pin "3") (pinfunction "3_3") (pintype "passive"))
    )
    (net (code "58") (name "Net-(RELE_IN_AUDIO1B-P)") (class "Default")
      (node (ref "R36") (pin "2") (pinfunction "2_2") (pintype "passive"))
      (node (ref "RELE_IN_AUDIO1") (pin "4") (pinfunction "P_4") (pintype "passive"))
    )
    (net (code "59") (name "Net-(RELE_IN_AUDIO1B-S)") (class "Default")
      (node (ref "RELE_IN_AUDIO1") (pin "8") (pinfunction "S_8") (pintype "passive"))
      (node (ref "VOLUME") (pin "3") (pinfunction "3_3") (pintype "passive"))
    )
    (net (code "60") (name "Net-(RL_FIM_INFERIORB-P)") (class "Default")
      (node (ref "CTT-DESCE") (pin "2") (pinfunction "2_2") (pintype "passive"))
      (node (ref "D2") (pin "C") (pinfunction "C_C") (pintype "passive"))
      (node (ref "RL_FIM_INFERIOR") (pin "4") (pinfunction "P_4") (pintype "passive"))
    )
    (net (code "61") (name "Net-(RL_FIM_SUPERIORB-P)") (class "Default")
      (node (ref "CTT-SOBE") (pin "2") (pinfunction "2_2") (pintype "passive"))
      (node (ref "D3") (pin "C") (pinfunction "C_C") (pintype "passive"))
      (node (ref "RL_FIM_SUPERIOR") (pin "4") (pinfunction "P_4") (pintype "passive"))
    )
    (net (code "62") (name "Net-(SAIDA_CANA-KL)") (class "Default")
      (node (ref "D5") (pin "A") (pinfunction "A_A") (pintype "passive"))
      (node (ref "D6") (pin "A") (pinfunction "A_A") (pintype "passive"))
      (node (ref "SAIDA_CAN") (pin "1") (pinfunction "KL_1") (pintype "passive"))
    )
    (net (code "63") (name "Net-(SAIDA_CANB-KL)") (class "Default")
      (node (ref "D15") (pin "C") (pinfunction "C_C") (pintype "passive"))
      (node (ref "D4") (pin "C") (pinfunction "C_C") (pintype "passive"))
      (node (ref "SAIDA_CAN") (pin "2") (pinfunction "KL_2") (pintype "passive"))
    )
    (net (code "64") (name "Net-(SOBE-C)") (class "Default")
      (node (ref "R13") (pin "1") (pinfunction "1_1") (pintype "passive"))
      (node (ref "SOBE") (pin "K") (pinfunction "C_K") (pintype "passive"))
    )
    (net (code "65") (name "Net-(T1-B)") (class "Default")
      (node (ref "R1") (pin "1") (pinfunction "1_1") (pintype "passive"))
      (node (ref "T1") (pin "1") (pinfunction "B_1") (pintype "passive"))
    )
    (net (code "66") (name "Net-(TRAFO_CANA-KL)") (class "Default")
      (node (ref "F1_CANCELAS") (pin "1") (pinfunction "1_1") (pintype "passive"))
      (node (ref "TRAFO_CAN") (pin "1") (pinfunction "KL_1") (pintype "passive"))
    )
    (net (code "67") (name "Net-(TRAFO_CANB-KL)") (class "Default")
      (node (ref "D15") (pin "A") (pinfunction "A_A") (pintype "passive"))
      (node (ref "D6") (pin "C") (pinfunction "C_C") (pintype "passive"))
      (node (ref "TRAFO_CAN") (pin "2") (pinfunction "KL_2") (pintype "passive"))
    )
    (net (code "68") (name "Net-(VREG1-IN)") (class "Default")
      (node (ref "C8") (pin "+") (pinfunction "+_+") (pintype "passive"))
      (node (ref "D11") (pin "C") (pinfunction "C_C") (pintype "passive"))
      (node (ref "D12") (pin "C") (pinfunction "C_C") (pintype "passive"))
      (node (ref "VREG1") (pin "1") (pinfunction "IN_1") (pintype "power_in"))
    )
    (net (code "69") (name "OPT_AUDIO_FALA") (class "Default")
      (node (ref "COM1") (pin "16") (pinfunction "16_16") (pintype "passive"))
      (node (ref "ULN1") (pin "1") (pinfunction "1_1") (pintype "bidirectional"))
    )
    (net (code "70") (name "OPT_AUDIO_LIGA") (class "Default")
      (node (ref "COM1") (pin "14") (pinfunction "14_14") (pintype "passive"))
      (node (ref "R50") (pin "2") (pinfunction "2_2") (pintype "passive"))
    )
    (net (code "71") (name "OPT_DESCE") (class "Default")
      (node (ref "COM1") (pin "10") (pinfunction "10_10") (pintype "passive"))
      (node (ref "ULN1") (pin "3") (pinfunction "3_3") (pintype "bidirectional"))
    )
    (net (code "72") (name "OPT_FREIO") (class "Default")
      (node (ref "COM1") (pin "8") (pinfunction "8_8") (pintype "passive"))
      (node (ref "ULN1") (pin "4") (pinfunction "4_4") (pintype "bidirectional"))
    )
    (net (code "73") (name "OPT_LIGA") (class "Default")
      (node (ref "COM1") (pin "6") (pinfunction "6_6") (pintype "passive"))
      (node (ref "ULN1") (pin "5") (pinfunction "5_5") (pintype "bidirectional"))
    )
    (net (code "74") (name "OPT_SOBE") (class "Default")
      (node (ref "COM1") (pin "12") (pinfunction "12_12") (pintype "passive"))
      (node (ref "ULN1") (pin "2") (pinfunction "2_2") (pintype "bidirectional"))
    )
    (net (code "75") (name "PANTOGRAFICA") (class "Default")
      (node (ref "PORTA_CABINE") (pin "11") (pinfunction "O_11") (pintype "passive"))
      (node (ref "R23") (pin "2") (pinfunction "2_2") (pintype "passive"))
    )
    (net (code "76") (name "PORTA_CABINE") (class "Default")
      (node (ref "PORTA") (pin "1") (pinfunction "KL_1") (pintype "passive"))
      (node (ref "R12") (pin "2") (pinfunction "2_2") (pintype "passive"))
      (node (ref "ULN1") (pin "8") (pinfunction "8_8") (pintype "bidirectional"))
    )
    (net (code "77") (name "RELE_FALAR") (class "Default")
      (node (ref "RELE_IN_AUDIO") (pin "1") (pinfunction "+_1") (pintype "passive"))
      (node (ref "RELE_IN_AUDIO1") (pin "1") (pinfunction "+_1") (pintype "passive"))
      (node (ref "ULN1") (pin "18") (pinfunction "18_18") (pintype "bidirectional"))
    )
    (net (code "78") (name "RL_INF") (class "Default")
      (node (ref "RL_FIM_INFERIOR") (pin "16") (pinfunction "-_16") (pintype "passive"))
      (node (ref "ULN1") (pin "12") (pinfunction "12_12") (pintype "bidirectional"))
    )
    (net (code "79") (name "RL_PT_CABINE") (class "Default")
      (node (ref "PORTA_CABINE") (pin "16") (pinfunction "-_16") (pintype "passive"))
      (node (ref "ULN1") (pin "11") (pinfunction "11_11") (pintype "bidirectional"))
    )
    (net (code "80") (name "RL_SUP") (class "Default")
      (node (ref "RL_FIM_SUPERIOR") (pin "16") (pinfunction "-_16") (pintype "passive"))
      (node (ref "ULN1") (pin "13") (pinfunction "13_13") (pintype "bidirectional"))
    )
    (net (code "81") (name "RS485-A") (class "Default")
      (node (ref "COM1") (pin "17") (pinfunction "17_17") (pintype "passive"))
      (node (ref "U$1") (pin "2") (pinfunction "2_2") (pintype "bidirectional"))
      (node (ref "X1") (pin "2") (pinfunction "KL_2") (pintype "passive"))
    )
    (net (code "82") (name "RS485-B") (class "Default")
      (node (ref "COM1") (pin "19") (pinfunction "19_19") (pintype "passive"))
      (node (ref "U$1") (pin "1") (pinfunction "1_1") (pintype "bidirectional"))
      (node (ref "X1") (pin "1") (pinfunction "KL_1") (pintype "passive"))
    )
    (net (code "83") (name "SAIDA-AUDIO") (class "Default")
      (node (ref "C1") (pin "-") (pinfunction "-_-") (pintype "passive"))
      (node (ref "RELE_IN_AUDIO") (pin "6") (pinfunction "O_6") (pintype "passive"))
      (node (ref "RELE_IN_AUDIO") (pin "9") (pinfunction "S_9") (pintype "passive"))
    )
    (net (code "84") (name "SENSOR1") (class "Default")
      (node (ref "R9") (pin "2") (pinfunction "2_2") (pintype "passive"))
      (node (ref "S2") (pin "1") (pinfunction "KL_1") (pintype "passive"))
    )
    (net (code "85") (name "SENSOR2") (class "Default")
      (node (ref "R24") (pin "2") (pinfunction "2_2") (pintype "passive"))
      (node (ref "S3") (pin "1") (pinfunction "KL_1") (pintype "passive"))
    )
    (net (code "86") (name "SENSOR3") (class "Default")
      (node (ref "R25") (pin "2") (pinfunction "2_2") (pintype "passive"))
      (node (ref "S4") (pin "1") (pinfunction "KL_1") (pintype "passive"))
    )
    (net (code "87") (name "SUP") (class "Default")
      (node (ref "R10") (pin "2") (pinfunction "2_2") (pintype "passive"))
      (node (ref "U$1") (pin "3") (pinfunction "3_3") (pintype "bidirectional"))
      (node (ref "ULN1") (pin "6") (pinfunction "6_6") (pintype "bidirectional"))
      (node (ref "X1") (pin "3") (pinfunction "KL_3") (pintype "passive"))
    )
    (net (code "88") (name "unconnected-(CTT-FREIO-PadO)") (class "Default")
      (node (ref "CTT-FREIO") (pin "O") (pinfunction "O_O") (pintype "passive"))
    )
    (net (code "89") (name "unconnected-(CTT-LIGA-PadO)") (class "Default")
      (node (ref "CTT-LIGA") (pin "O") (pinfunction "O_O") (pintype "passive"))
    )
    (net (code "90") (name "unconnected-(PORTA_CABINEB-S-Pad8)") (class "Default")
      (node (ref "PORTA_CABINE") (pin "8") (pinfunction "S_8") (pintype "passive"))
    )
    (net (code "91") (name "unconnected-(PORTA_CABINEC-S-Pad9)") (class "Default")
      (node (ref "PORTA_CABINE") (pin "9") (pinfunction "S_9") (pintype "passive"))
    )
    (net (code "92") (name "unconnected-(RL_FIM_INFERIORB-S-Pad8)") (class "Default")
      (node (ref "RL_FIM_INFERIOR") (pin "8") (pinfunction "S_8") (pintype "passive"))
    )
    (net (code "93") (name "unconnected-(RL_FIM_INFERIORC-S-Pad9)") (class "Default")
      (node (ref "RL_FIM_INFERIOR") (pin "9") (pinfunction "S_9") (pintype "passive"))
    )
    (net (code "94") (name "unconnected-(RL_FIM_SUPERIORB-S-Pad8)") (class "Default")
      (node (ref "RL_FIM_SUPERIOR") (pin "8") (pinfunction "S_8") (pintype "passive"))
    )
    (net (code "95") (name "unconnected-(RL_FIM_SUPERIORC-S-Pad9)") (class "Default")
      (node (ref "RL_FIM_SUPERIOR") (pin "9") (pinfunction "S_9") (pintype "passive"))
    )
  )
)
